# k-line-adapter.net
KiCad netlist of a schematic drawn in EAGLE
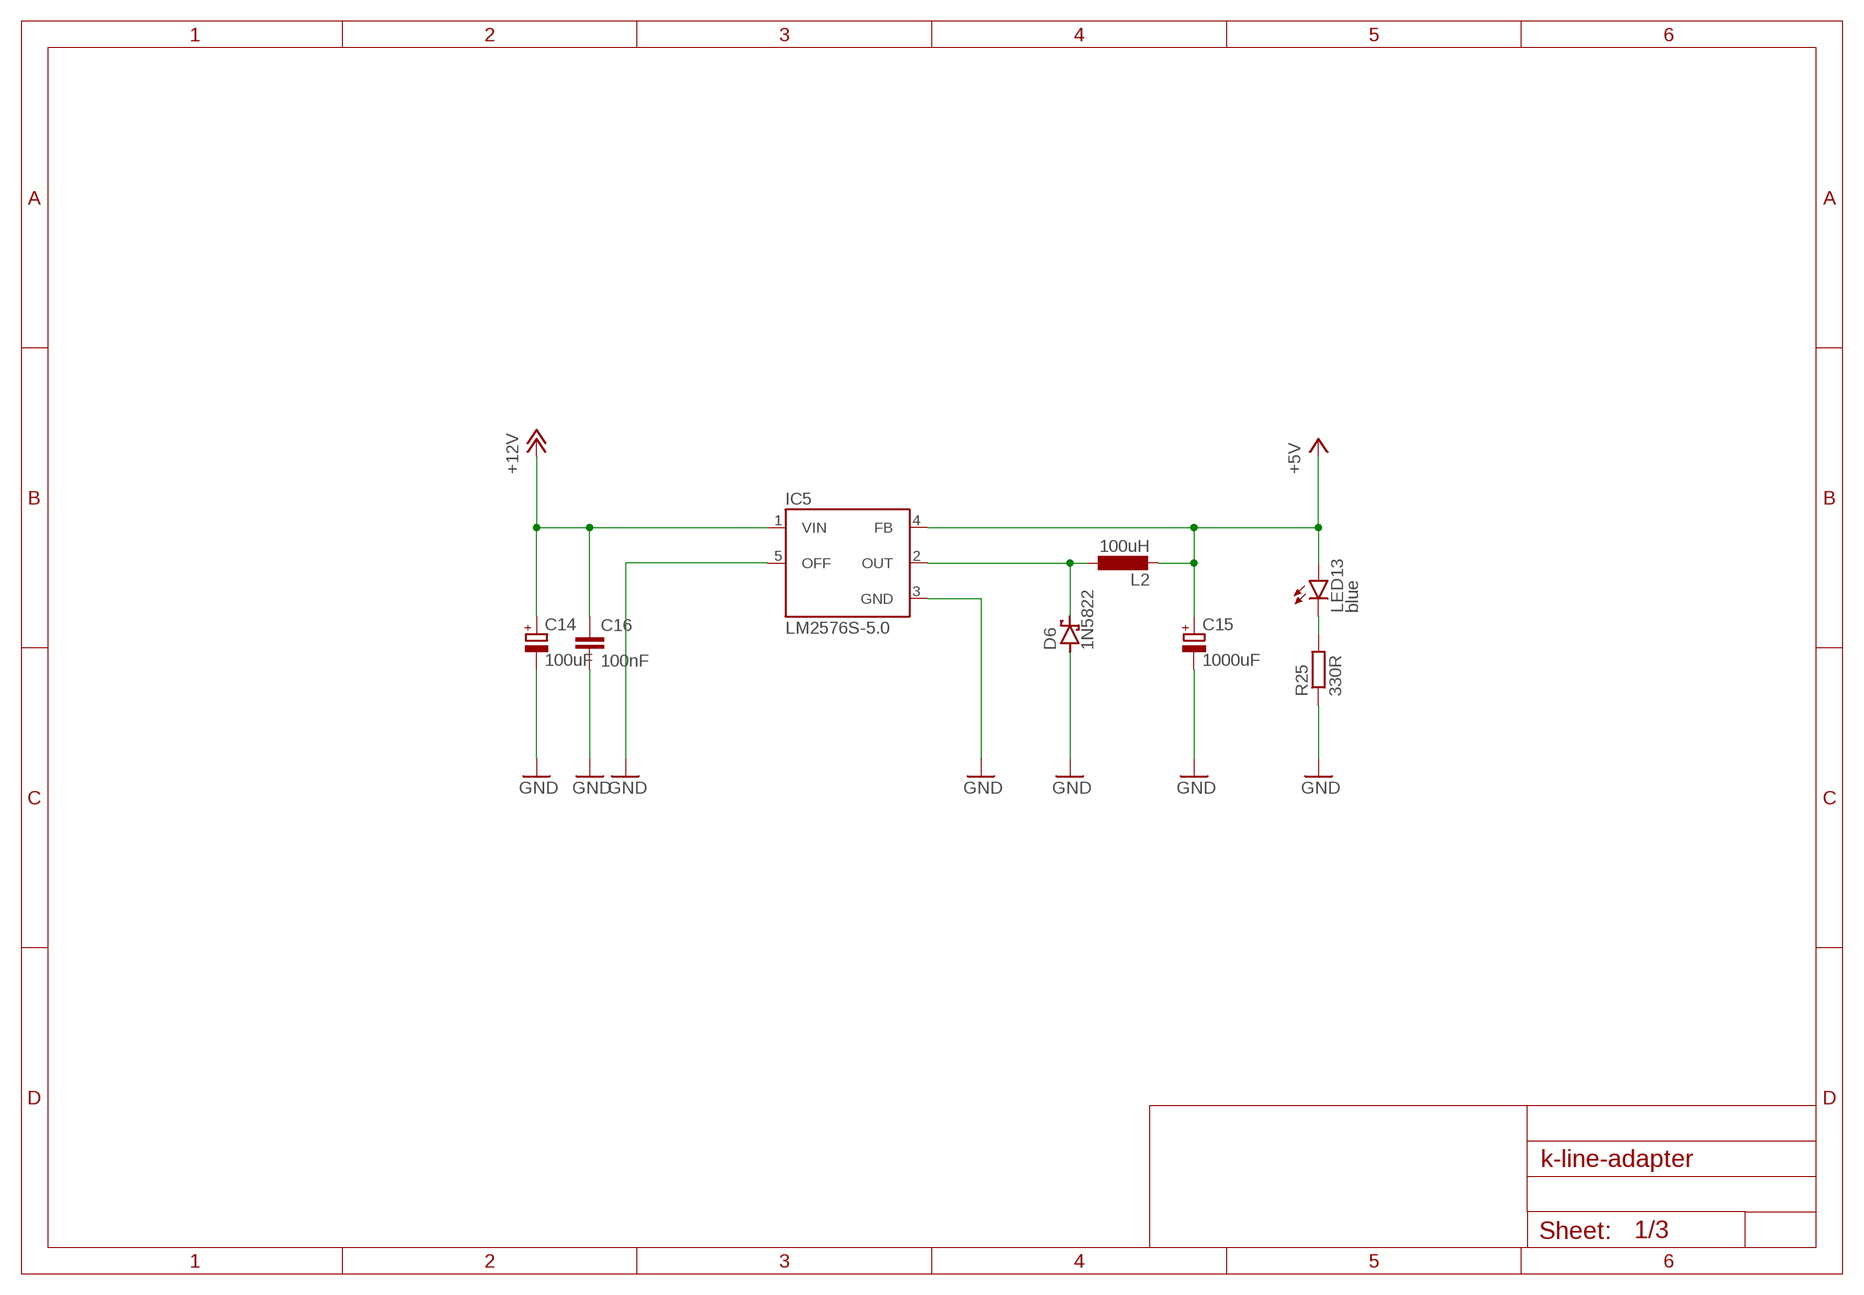
[diagram p0: schematic, sheet 1]
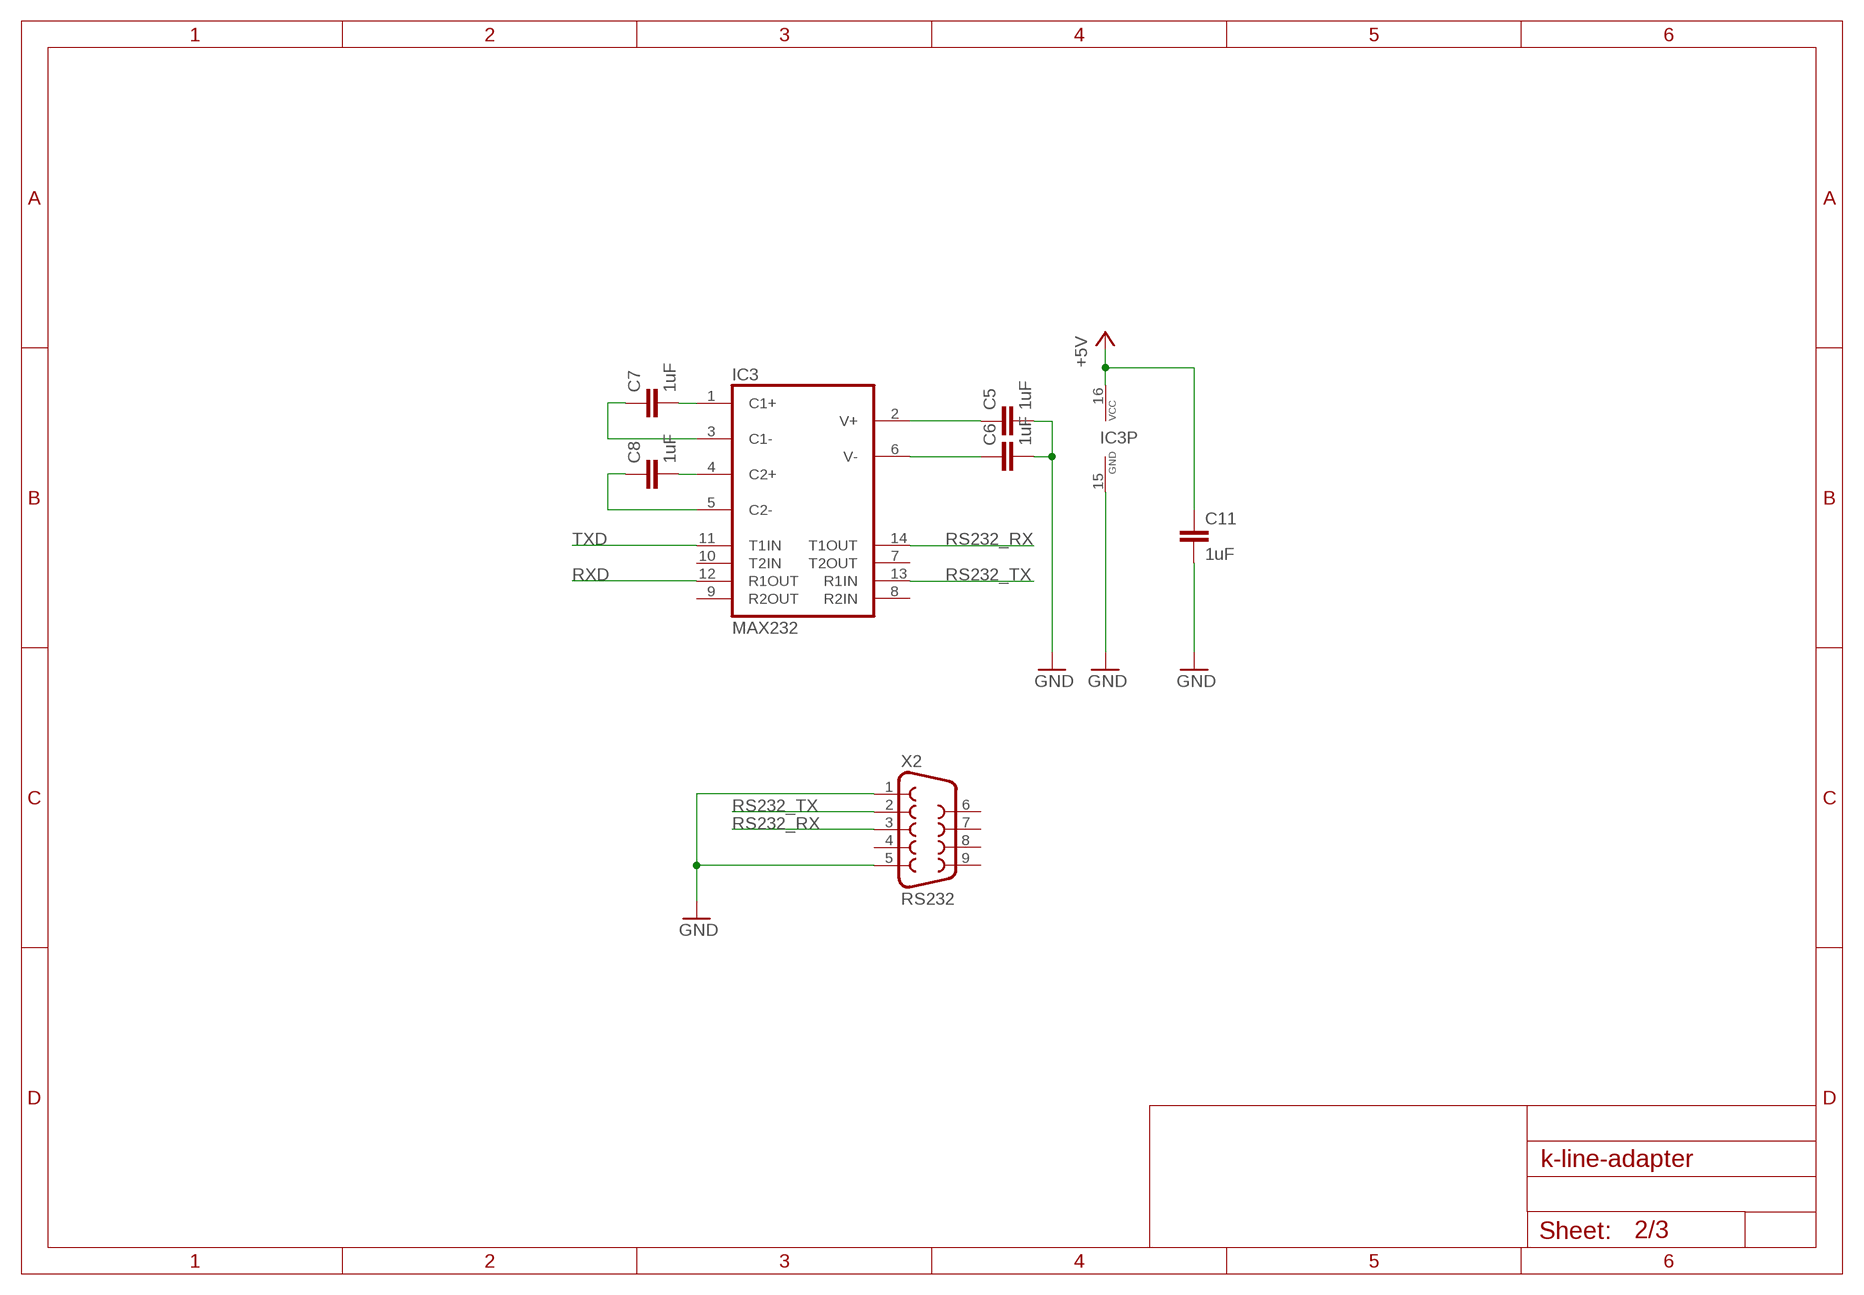
[diagram p1: schematic, sheet 2]
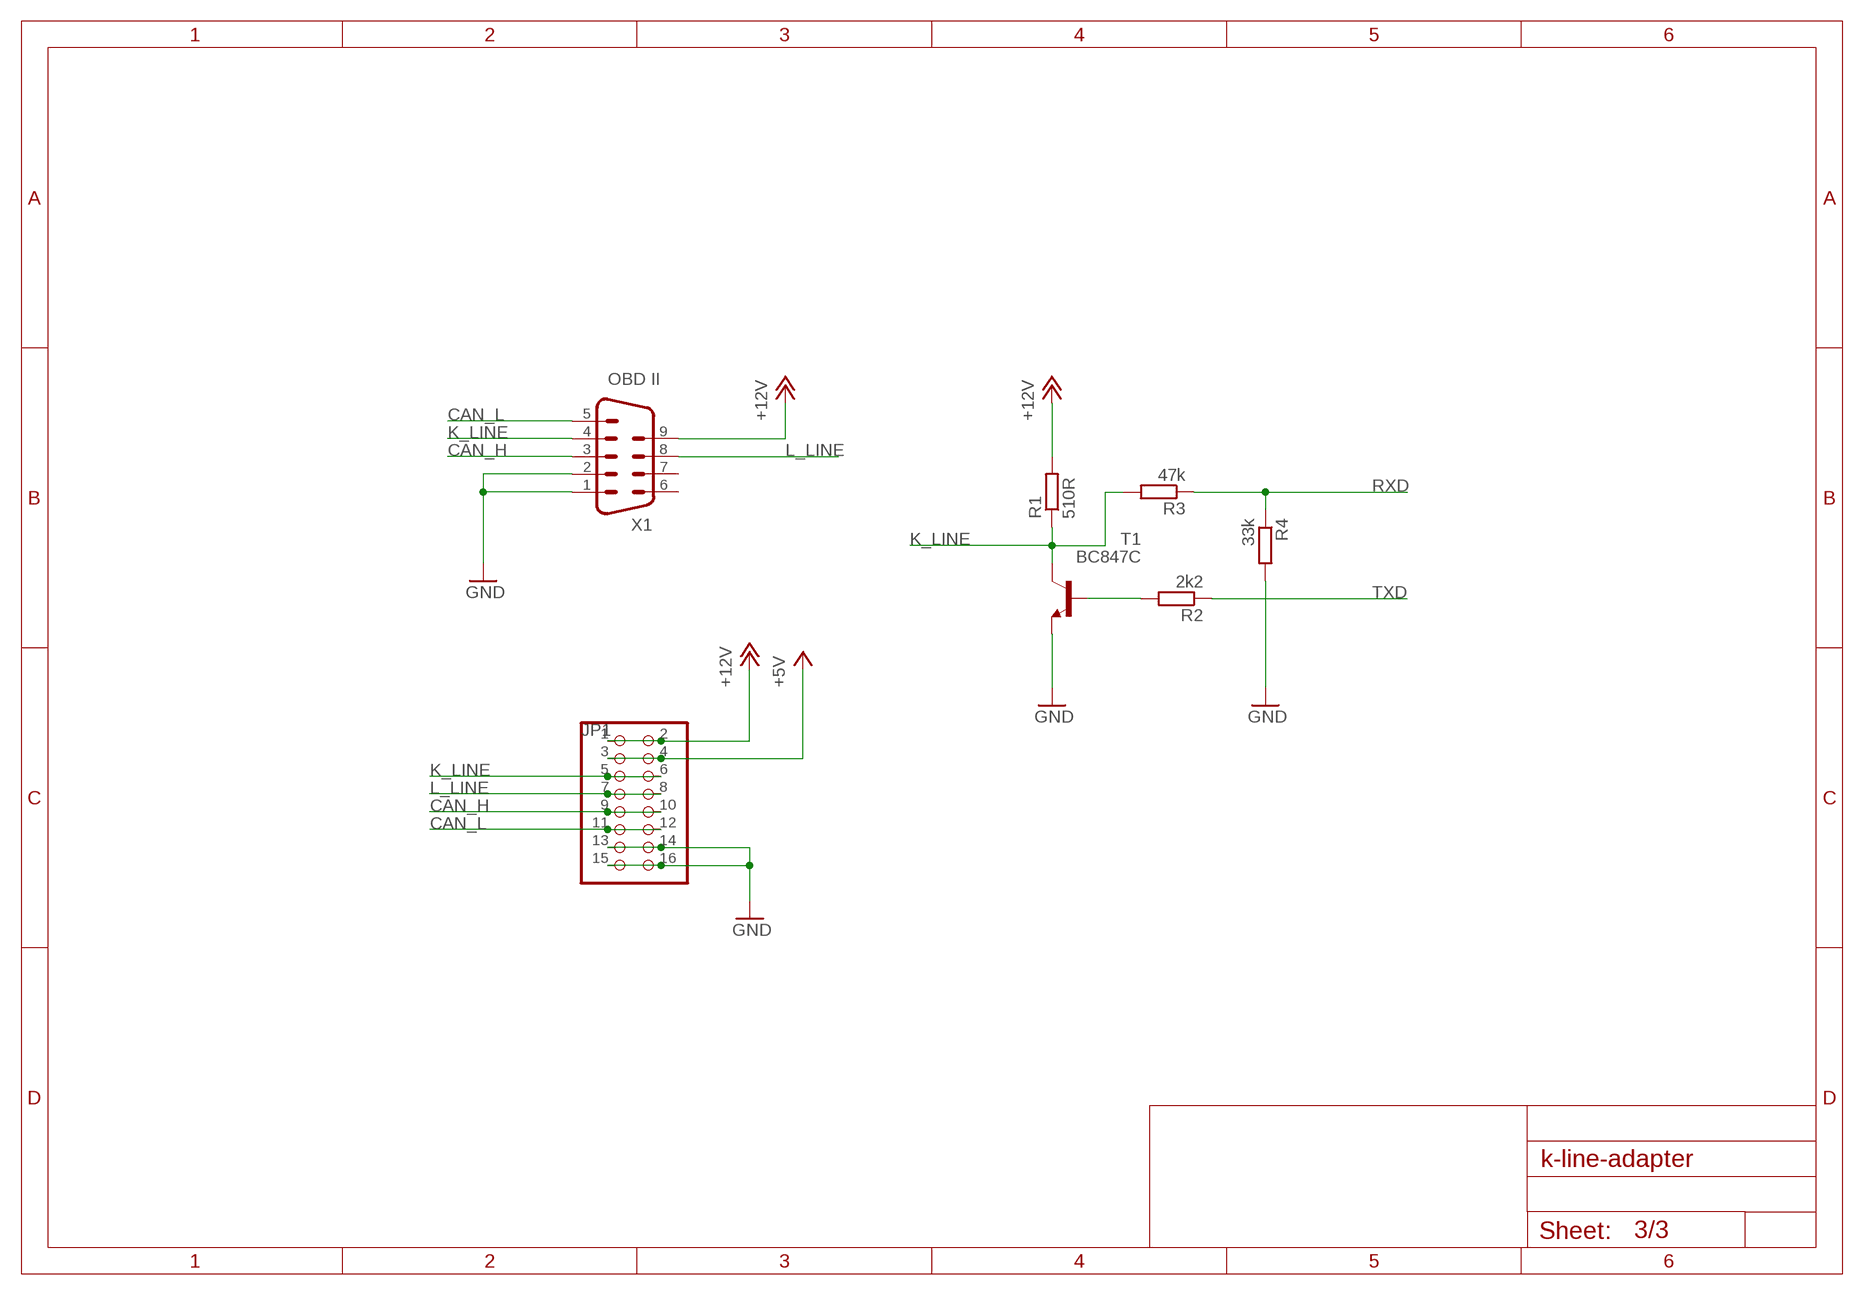
[diagram p2: schematic, sheet 3]

(export (version "E")
  (design (tool "Eeschema 10.0.6"))
  (components
    (comp (ref "C14")
      (value "100uF")
      (footprint "eagle-import:E5-10,5")
      (libsource (lib "eagle-import") (part "CPOL-EUE5-10.5"))
    )
    (comp (ref "C15")
      (value "1000uF")
      (footprint "eagle-import:E5-10,5")
      (libsource (lib "eagle-import") (part "CPOL-EUE5-10.5"))
    )
    (comp (ref "C16")
      (value "100nF")
      (footprint "eagle-import:C0805")
      (libsource (lib "eagle-import") (part "C-EUC0805"))
    )
    (comp (ref "D6")
      (value "1N5822")
      (footprint "eagle-import:DO201T15")
      (libsource (lib "eagle-import") (part "SCHOTTKY-DIODEDO201T15"))
    )
    (comp (ref "IC5")
      (value "LM2576S-5.0")
      (footprint "eagle-import:TO263-5")
      (libsource (lib "eagle-import") (part "LM2576S"))
    )
    (comp (ref "L2")
      (value "100uH")
      (footprint "eagle-import:09HCP")
      (libsource (lib "eagle-import") (part "L-LEU-09HCP"))
    )
    (comp (ref "LED13")
      (value "blue")
      (footprint "eagle-import:CHIP-LED0805")
      (libsource (lib "eagle-import") (part "LEDCHIP-LED0805"))
    )
    (comp (ref "R25")
      (value "330R")
      (footprint "eagle-import:R0805")
      (libsource (lib "eagle-import") (part "R-EU_R0805"))
    )
    (comp (ref "JP1")
      (value "PINHD-2X8")
      (footprint "eagle-import:2X08")
      (libsource (lib "eagle-import") (part "PINHD-2X8"))
    )
    (comp (ref "R1")
      (value "510R")
      (footprint "eagle-import:R0805")
      (libsource (lib "eagle-import") (part "R-EU_R0805"))
    )
    (comp (ref "R2")
      (value "2k2")
      (footprint "eagle-import:R0805")
      (libsource (lib "eagle-import") (part "R-EU_R0805"))
    )
    (comp (ref "R3")
      (value "47k")
      (footprint "eagle-import:R0805")
      (libsource (lib "eagle-import") (part "R-EU_R0805"))
    )
    (comp (ref "R4")
      (value "33k")
      (footprint "eagle-import:R0805")
      (libsource (lib "eagle-import") (part "R-EU_R0805"))
    )
    (comp (ref "T1")
      (value "BC847C")
      (footprint "eagle-import:SOT23-BEC")
      (libsource (lib "eagle-import") (part "-NPN-SOT23-BECBC847C"))
    )
    (comp (ref "X1")
      (value "M09HP")
      (footprint "eagle-import:M09HP")
      (libsource (lib "eagle-import") (part "M09HP"))
    )
    (comp (ref "C5")
      (value "1uF")
      (footprint "eagle-import:C0805")
      (libsource (lib "eagle-import") (part "C-EUC0805"))
    )
    (comp (ref "C6")
      (value "1uF")
      (footprint "eagle-import:C0805")
      (libsource (lib "eagle-import") (part "C-EUC0805"))
    )
    (comp (ref "C7")
      (value "1uF")
      (footprint "eagle-import:C0805")
      (libsource (lib "eagle-import") (part "C-EUC0805"))
    )
    (comp (ref "C8")
      (value "1uF")
      (footprint "eagle-import:C0805")
      (libsource (lib "eagle-import") (part "C-EUC0805"))
    )
    (comp (ref "C11")
      (value "1uF")
      (footprint "eagle-import:C0805")
      (libsource (lib "eagle-import") (part "C-EUC0805"))
    )
    (comp (ref "IC3")
      (value "MAX232")
      (footprint "eagle-import:DIL16")
      (fields (field (name "MF") "MAXIM") (field (name "MPN") "MAX232ACPE+"))
      (libsource (lib "eagle-import") (part "MAX232"))
    )
    (comp (ref "X2")
      (value "RS232")
      (footprint "eagle-import:F09HP")
      (libsource (lib "eagle-import") (part "F09HP"))
    )
  )
  (nets
    (net (code "1") (name "+5V") (class "Default")
      (node (ref "C11") (pin "1") (pinfunction "1_1") (pintype "passive"))
      (node (ref "C15") (pin "+") (pinfunction "+_+") (pintype "passive"))
      (node (ref "IC3") (pin "16") (pinfunction "VCC_16") (pintype "power_in"))
      (node (ref "IC5") (pin "4") (pinfunction "FB_4") (pintype "input"))
      (node (ref "JP1") (pin "3") (pinfunction "3_3") (pintype "passive"))
      (node (ref "JP1") (pin "4") (pinfunction "4_4") (pintype "passive"))
      (node (ref "L2") (pin "P$2") (pinfunction "2_P$2") (pintype "passive"))
      (node (ref "LED13") (pin "A") (pinfunction "A_A") (pintype "passive"))
    )
    (net (code "2") (name "+12V") (class "Default")
      (node (ref "C14") (pin "+") (pinfunction "+_+") (pintype "passive"))
      (node (ref "C16") (pin "1") (pinfunction "1_1") (pintype "passive"))
      (node (ref "IC5") (pin "1") (pinfunction "VIN_1") (pintype "power_in"))
      (node (ref "JP1") (pin "1") (pinfunction "1_1") (pintype "passive"))
      (node (ref "JP1") (pin "2") (pinfunction "2_2") (pintype "passive"))
      (node (ref "R1") (pin "2") (pinfunction "2_2") (pintype "passive"))
      (node (ref "X1") (pin "9") (pinfunction "9_9") (pintype "passive"))
    )
    (net (code "3") (name "CAN_H") (class "Default")
      (node (ref "JP1") (pin "10") (pinfunction "10_10") (pintype "passive"))
      (node (ref "JP1") (pin "9") (pinfunction "9_9") (pintype "passive"))
      (node (ref "X1") (pin "3") (pinfunction "3_3") (pintype "passive"))
    )
    (net (code "4") (name "CAN_L") (class "Default")
      (node (ref "JP1") (pin "11") (pinfunction "11_11") (pintype "passive"))
      (node (ref "JP1") (pin "12") (pinfunction "12_12") (pintype "passive"))
      (node (ref "X1") (pin "5") (pinfunction "5_5") (pintype "passive"))
    )
    (net (code "5") (name "GND") (class "Default")
      (node (ref "C11") (pin "2") (pinfunction "2_2") (pintype "passive"))
      (node (ref "C14") (pin "-") (pinfunction "-_-") (pintype "passive"))
      (node (ref "C15") (pin "-") (pinfunction "-_-") (pintype "passive"))
      (node (ref "C16") (pin "2") (pinfunction "2_2") (pintype "passive"))
      (node (ref "C5") (pin "2") (pinfunction "2_2") (pintype "passive"))
      (node (ref "C6") (pin "2") (pinfunction "2_2") (pintype "passive"))
      (node (ref "D6") (pin "A") (pinfunction "A_A") (pintype "passive"))
      (node (ref "IC3") (pin "15") (pinfunction "GND_15") (pintype "power_in"))
      (node (ref "IC5") (pin "3") (pinfunction "GND_3") (pintype "power_in"))
      (node (ref "IC5") (pin "5") (pinfunction "OFF_5") (pintype "input"))
      (node (ref "JP1") (pin "13") (pinfunction "13_13") (pintype "passive"))
      (node (ref "JP1") (pin "14") (pinfunction "14_14") (pintype "passive"))
      (node (ref "JP1") (pin "15") (pinfunction "15_15") (pintype "passive"))
      (node (ref "JP1") (pin "16") (pinfunction "16_16") (pintype "passive"))
      (node (ref "R25") (pin "1") (pinfunction "1_1") (pintype "passive"))
      (node (ref "R4") (pin "2") (pinfunction "2_2") (pintype "passive"))
      (node (ref "T1") (pin "E") (pinfunction "E_E") (pintype "passive"))
      (node (ref "X1") (pin "1") (pinfunction "1_1") (pintype "passive"))
      (node (ref "X1") (pin "2") (pinfunction "2_2") (pintype "passive"))
      (node (ref "X2") (pin "1") (pinfunction "1_1") (pintype "passive"))
      (node (ref "X2") (pin "5") (pinfunction "5_5") (pintype "passive"))
    )
    (net (code "6") (name "K_LINE") (class "Default")
      (node (ref "JP1") (pin "5") (pinfunction "5_5") (pintype "passive"))
      (node (ref "JP1") (pin "6") (pinfunction "6_6") (pintype "passive"))
      (node (ref "R1") (pin "1") (pinfunction "1_1") (pintype "passive"))
      (node (ref "R3") (pin "2") (pinfunction "2_2") (pintype "passive"))
      (node (ref "T1") (pin "C") (pinfunction "C_C") (pintype "passive"))
      (node (ref "X1") (pin "4") (pinfunction "4_4") (pintype "passive"))
    )
    (net (code "7") (name "L_LINE") (class "Default")
      (node (ref "JP1") (pin "7") (pinfunction "7_7") (pintype "passive"))
      (node (ref "JP1") (pin "8") (pinfunction "8_8") (pintype "passive"))
      (node (ref "X1") (pin "8") (pinfunction "8_8") (pintype "passive"))
    )
    (net (code "8") (name "Net-(IC3A-C1+)") (class "Default")
      (node (ref "C7") (pin "2") (pinfunction "2_2") (pintype "passive"))
      (node (ref "IC3") (pin "1") (pinfunction "C1+_1") (pintype "bidirectional"))
    )
    (net (code "9") (name "Net-(IC3A-C1-)") (class "Default")
      (node (ref "C7") (pin "1") (pinfunction "1_1") (pintype "passive"))
      (node (ref "IC3") (pin "3") (pinfunction "C1-_3") (pintype "bidirectional"))
    )
    (net (code "10") (name "Net-(IC3A-C2+)") (class "Default")
      (node (ref "C8") (pin "2") (pinfunction "2_2") (pintype "passive"))
      (node (ref "IC3") (pin "4") (pinfunction "C2+_4") (pintype "bidirectional"))
    )
    (net (code "11") (name "Net-(IC3A-C2-)") (class "Default")
      (node (ref "C8") (pin "1") (pinfunction "1_1") (pintype "passive"))
      (node (ref "IC3") (pin "5") (pinfunction "C2-_5") (pintype "bidirectional"))
    )
    (net (code "12") (name "Net-(IC3A-V+)") (class "Default")
      (node (ref "C5") (pin "1") (pinfunction "1_1") (pintype "passive"))
      (node (ref "IC3") (pin "2") (pinfunction "V+_2") (pintype "bidirectional"))
    )
    (net (code "13") (name "Net-(IC3A-V-)") (class "Default")
      (node (ref "C6") (pin "1") (pinfunction "1_1") (pintype "passive"))
      (node (ref "IC3") (pin "6") (pinfunction "V-_6") (pintype "bidirectional"))
    )
    (net (code "14") (name "Net-(IC5-OUT)") (class "Default")
      (node (ref "D6") (pin "C") (pinfunction "C_C") (pintype "passive"))
      (node (ref "IC5") (pin "2") (pinfunction "OUT_2") (pintype "output"))
      (node (ref "L2") (pin "P$1") (pinfunction "1_P$1") (pintype "passive"))
    )
    (net (code "15") (name "Net-(LED13-PadC)") (class "Default")
      (node (ref "LED13") (pin "C") (pinfunction "C_C") (pintype "passive"))
      (node (ref "R25") (pin "2") (pinfunction "2_2") (pintype "passive"))
    )
    (net (code "16") (name "Net-(R2-Pad2)") (class "Default")
      (node (ref "R2") (pin "2") (pinfunction "2_2") (pintype "passive"))
      (node (ref "T1") (pin "B") (pinfunction "B_B") (pintype "passive"))
    )
    (net (code "17") (name "RS232_RX") (class "Default")
      (node (ref "IC3") (pin "14") (pinfunction "T1OUT_14") (pintype "output"))
      (node (ref "X2") (pin "3") (pinfunction "3_3") (pintype "passive"))
    )
    (net (code "18") (name "RS232_TX") (class "Default")
      (node (ref "IC3") (pin "13") (pinfunction "R1IN_13") (pintype "input"))
      (node (ref "X2") (pin "2") (pinfunction "2_2") (pintype "passive"))
    )
    (net (code "19") (name "RXD") (class "Default")
      (node (ref "IC3") (pin "12") (pinfunction "R1OUT_12") (pintype "output"))
      (node (ref "R3") (pin "1") (pinfunction "1_1") (pintype "passive"))
      (node (ref "R4") (pin "1") (pinfunction "1_1") (pintype "passive"))
    )
    (net (code "20") (name "TXD") (class "Default")
      (node (ref "IC3") (pin "11") (pinfunction "T1IN_11") (pintype "input"))
      (node (ref "R2") (pin "1") (pinfunction "1_1") (pintype "passive"))
    )
    (net (code "21") (name "unconnected-(IC3A-R2IN-Pad8)") (class "Default")
      (node (ref "IC3") (pin "8") (pinfunction "R2IN_8") (pintype "input"))
    )
    (net (code "22") (name "unconnected-(IC3A-R2OUT-Pad9)") (class "Default")
      (node (ref "IC3") (pin "9") (pinfunction "R2OUT_9") (pintype "output"))
    )
    (net (code "23") (name "unconnected-(IC3A-T2IN-Pad10)") (class "Default")
      (node (ref "IC3") (pin "10") (pinfunction "T2IN_10") (pintype "input"))
    )
    (net (code "24") (name "unconnected-(IC3A-T2OUT-Pad7)") (class "Default")
      (node (ref "IC3") (pin "7") (pinfunction "T2OUT_7") (pintype "output"))
    )
    (net (code "25") (name "unconnected-(X1-Pad6)") (class "Default")
      (node (ref "X1") (pin "6") (pinfunction "6_6") (pintype "passive"))
    )
    (net (code "26") (name "unconnected-(X1-Pad7)") (class "Default")
      (node (ref "X1") (pin "7") (pinfunction "7_7") (pintype "passive"))
    )
    (net (code "27") (name "unconnected-(X2-Pad4)") (class "Default")
      (node (ref "X2") (pin "4") (pinfunction "4_4") (pintype "passive"))
    )
    (net (code "28") (name "unconnected-(X2-Pad6)") (class "Default")
      (node (ref "X2") (pin "6") (pinfunction "6_6") (pintype "passive"))
    )
    (net (code "29") (name "unconnected-(X2-Pad7)") (class "Default")
      (node (ref "X2") (pin "7") (pinfunction "7_7") (pintype "passive"))
    )
    (net (code "30") (name "unconnected-(X2-Pad8)") (class "Default")
      (node (ref "X2") (pin "8") (pinfunction "8_8") (pintype "passive"))
    )
    (net (code "31") (name "unconnected-(X2-Pad9)") (class "Default")
      (node (ref "X2") (pin "9") (pinfunction "9_9") (pintype "passive"))
    )
  )
)
